# dtdsl.net
KiCad netlist of a schematic drawn in Altium Designer
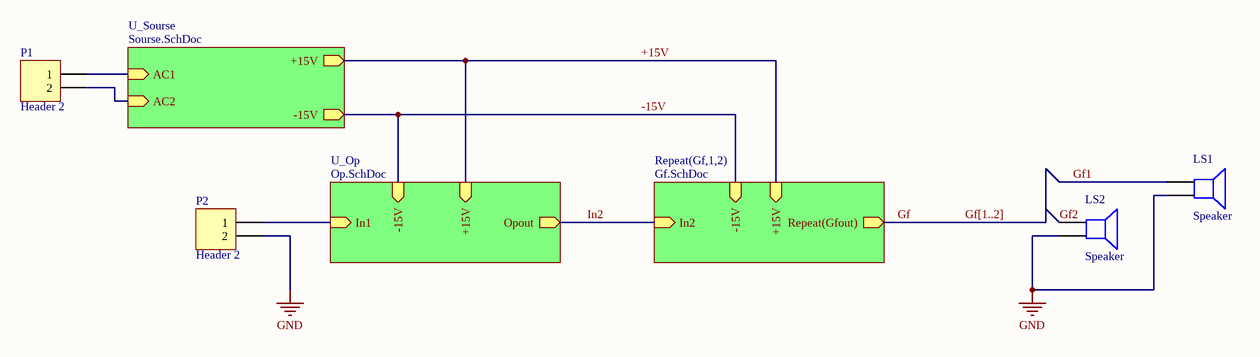
[diagram p0: dtdsl.SchDoc]

(export (version "E")
  (design (tool "Eeschema 10.0.6"))
  (components
    (comp (ref "LS1")
      (value "Speaker")
      (footprint "PIN2")
      (description "Loudspeaker")
      (fields (field (name "PUBLISHER") "Altium Limited"))
      (libsource (lib "Miscellaneous Devices") (part "Speaker"))
    )
    (comp (ref "LS2")
      (value "Speaker")
      (footprint "PIN2")
      (description "Loudspeaker")
      (fields (field (name "PUBLISHER") "Altium Limited"))
      (libsource (lib "Miscellaneous Devices") (part "Speaker"))
    )
    (comp (ref "P1")
      (value "Header 2")
      (footprint "HDR1X2")
      (description "Header, 2-Pin")
      (fields (field (name "PUBLISHER") "Altium Limited"))
      (libsource (lib "Miscellaneous Connectors") (part "Header 2"))
    )
    (comp (ref "P2")
      (value "Header 2")
      (footprint "HDR1X2")
      (description "Header, 2-Pin")
      (fields (field (name "PUBLISHER") "Altium Limited"))
      (libsource (lib "Miscellaneous Connectors") (part "Header 2"))
    )
  )
  (nets
    (net (code "3") (name "/AC1") (class "Default")
      (node (ref "P1") (pin "1") (pinfunction "1_1") (pintype "passive"))
    )
    (net (code "4") (name "/AC2") (class "Default")
      (node (ref "P1") (pin "2") (pinfunction "2_2") (pintype "passive"))
    )
    (net (code "6") (name "/Gf1") (class "Default")
      (node (ref "LS1") (pin "1") (pinfunction "1_1") (pintype "passive"))
    )
    (net (code "7") (name "/Gf2") (class "Default")
      (node (ref "LS2") (pin "1") (pinfunction "1_1") (pintype "passive"))
    )
    (net (code "9") (name "/In1") (class "Default")
      (node (ref "P2") (pin "1") (pinfunction "1_1") (pintype "passive"))
    )
    (net (code "11") (name "GND") (class "Default")
      (node (ref "LS1") (pin "2") (pinfunction "2_2") (pintype "passive"))
      (node (ref "LS2") (pin "2") (pinfunction "2_2") (pintype "passive"))
      (node (ref "P2") (pin "2") (pinfunction "2_2") (pintype "passive"))
    )
  )
)
